# Nixie6_IN-12A_1_0.net
KiCad netlist of a schematic drawn in EAGLE
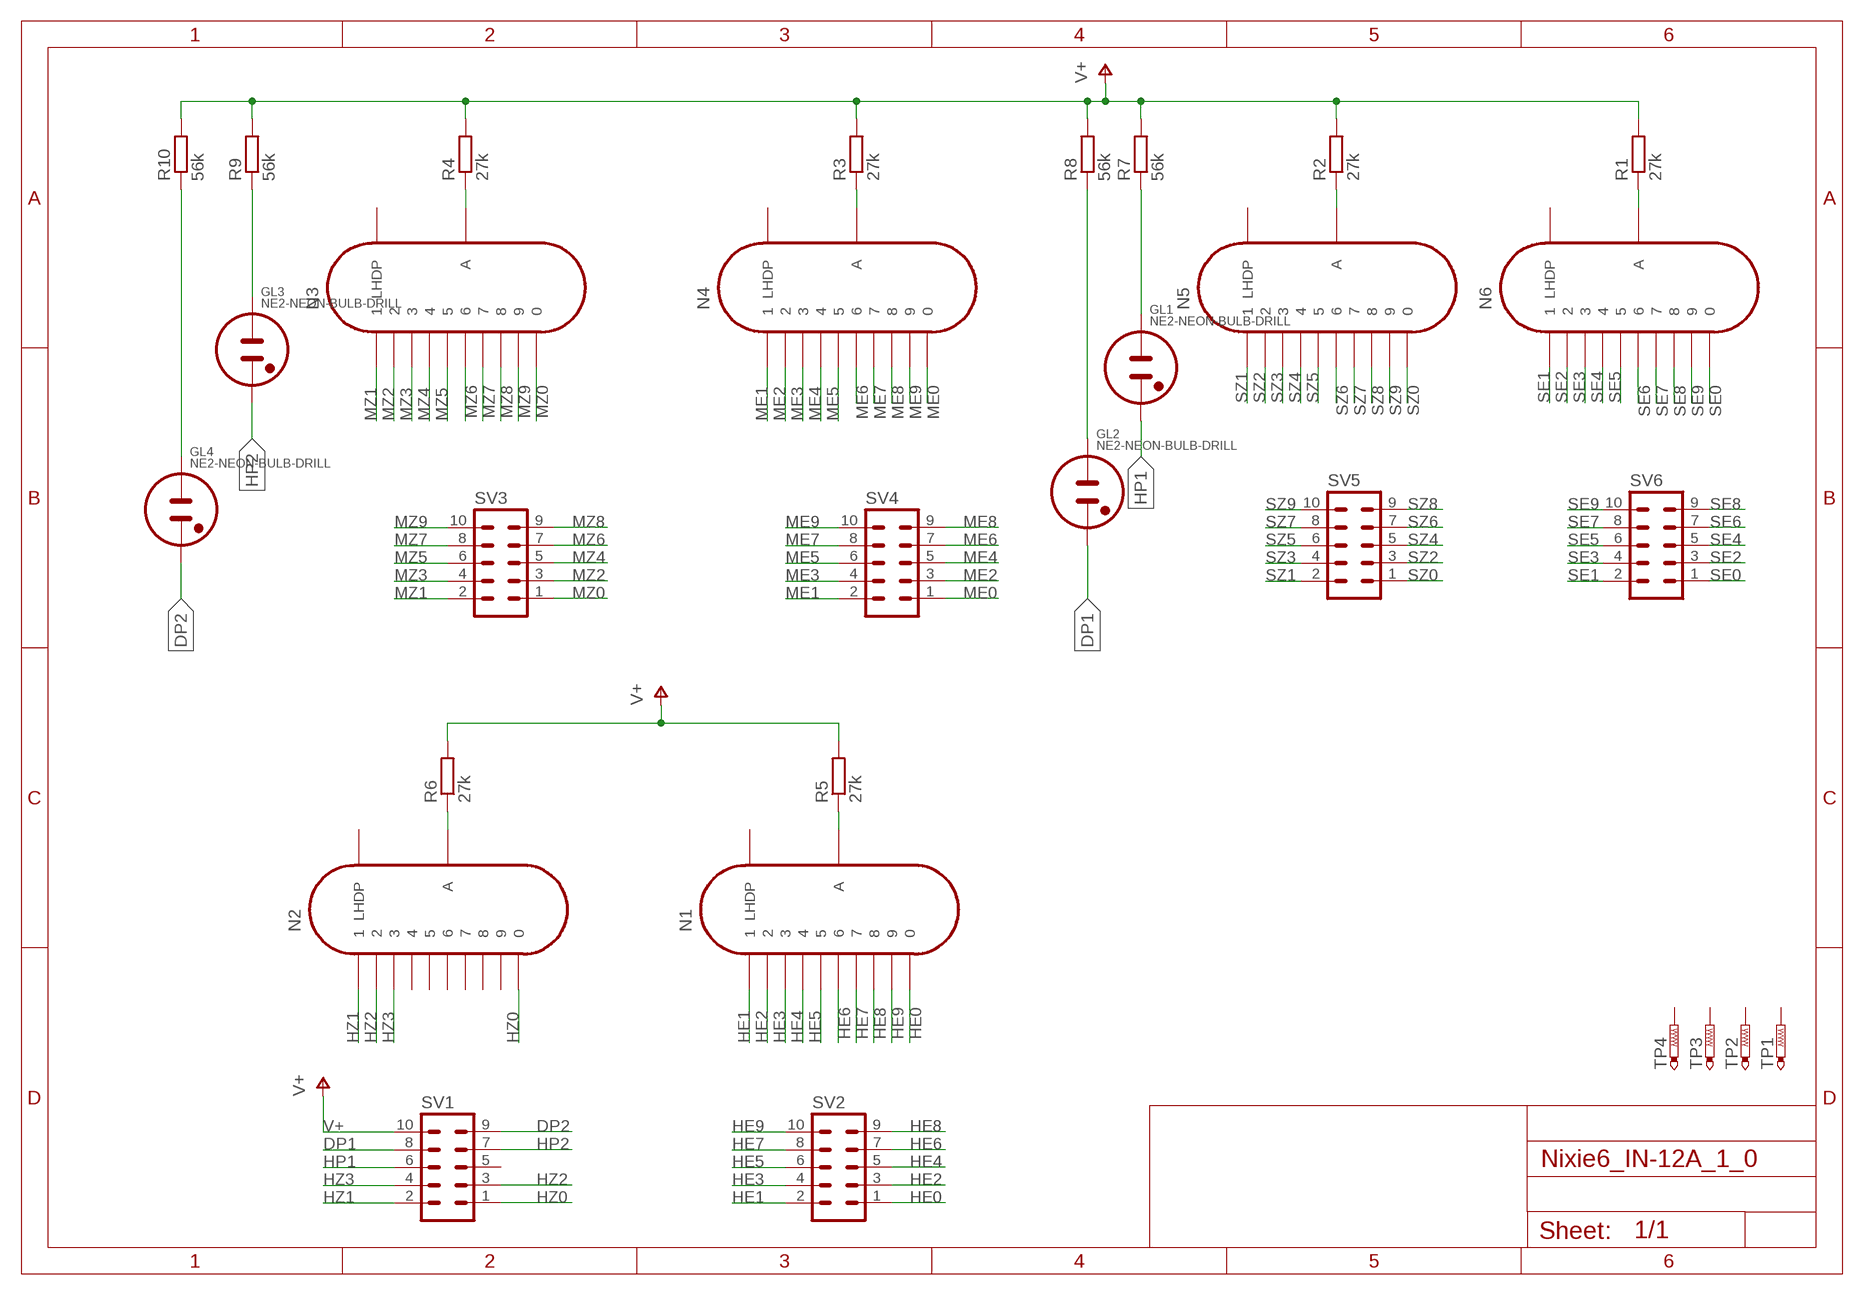
[diagram p0: schematic, sheet 1]

(export (version "E")
  (design (tool "Eeschema 10.0.6"))
  (components
    (comp (ref "GL1")
      (value "NE2-NEON-BULB-DRILL")
      (footprint "eagle-import:NE2-NEON-BULB-DRILL")
      (libsource (lib "eagle-import") (part "NE2-NEON-BULB-DRILL"))
    )
    (comp (ref "GL2")
      (value "NE2-NEON-BULB-DRILL")
      (footprint "eagle-import:NE2-NEON-BULB-DRILL")
      (libsource (lib "eagle-import") (part "NE2-NEON-BULB-DRILL"))
    )
    (comp (ref "GL3")
      (value "NE2-NEON-BULB-DRILL")
      (footprint "eagle-import:NE2-NEON-BULB-DRILL")
      (libsource (lib "eagle-import") (part "NE2-NEON-BULB-DRILL"))
    )
    (comp (ref "GL4")
      (value "NE2-NEON-BULB-DRILL")
      (footprint "eagle-import:NE2-NEON-BULB-DRILL")
      (libsource (lib "eagle-import") (part "NE2-NEON-BULB-DRILL"))
    )
    (comp (ref "N1")
      (value "IN-12B")
      (footprint "eagle-import:IN-12")
      (libsource (lib "eagle-import") (part "IN-12B"))
    )
    (comp (ref "N2")
      (value "IN-12B")
      (footprint "eagle-import:IN-12")
      (libsource (lib "eagle-import") (part "IN-12B"))
    )
    (comp (ref "N3")
      (value "IN-12B")
      (footprint "eagle-import:IN-12")
      (libsource (lib "eagle-import") (part "IN-12B"))
    )
    (comp (ref "N4")
      (value "IN-12B")
      (footprint "eagle-import:IN-12")
      (libsource (lib "eagle-import") (part "IN-12B"))
    )
    (comp (ref "N5")
      (value "IN-12B")
      (footprint "eagle-import:IN-12")
      (libsource (lib "eagle-import") (part "IN-12B"))
    )
    (comp (ref "N6")
      (value "IN-12B")
      (footprint "eagle-import:IN-12")
      (libsource (lib "eagle-import") (part "IN-12B"))
    )
    (comp (ref "R1")
      (value "27k")
      (footprint "eagle-import:0207_10")
      (libsource (lib "eagle-import") (part "R-EU_0207/10"))
    )
    (comp (ref "R2")
      (value "27k")
      (footprint "eagle-import:0207_10")
      (libsource (lib "eagle-import") (part "R-EU_0207/10"))
    )
    (comp (ref "R3")
      (value "27k")
      (footprint "eagle-import:0207_10")
      (libsource (lib "eagle-import") (part "R-EU_0207/10"))
    )
    (comp (ref "R4")
      (value "27k")
      (footprint "eagle-import:0207_10")
      (libsource (lib "eagle-import") (part "R-EU_0207/10"))
    )
    (comp (ref "R5")
      (value "27k")
      (footprint "eagle-import:0207_10")
      (libsource (lib "eagle-import") (part "R-EU_0207/10"))
    )
    (comp (ref "R6")
      (value "27k")
      (footprint "eagle-import:0207_10")
      (libsource (lib "eagle-import") (part "R-EU_0207/10"))
    )
    (comp (ref "R7")
      (value "56k")
      (footprint "eagle-import:0207_10")
      (libsource (lib "eagle-import") (part "R-EU_0207/10"))
    )
    (comp (ref "R8")
      (value "56k")
      (footprint "eagle-import:0207_10")
      (libsource (lib "eagle-import") (part "R-EU_0207/10"))
    )
    (comp (ref "R9")
      (value "56k")
      (footprint "eagle-import:0207_10")
      (libsource (lib "eagle-import") (part "R-EU_0207/10"))
    )
    (comp (ref "R10")
      (value "56k")
      (footprint "eagle-import:0207_10")
      (libsource (lib "eagle-import") (part "R-EU_0207/10"))
    )
    (comp (ref "SV1")
      (value "ML10")
      (footprint "eagle-import:ML10")
      (libsource (lib "eagle-import") (part "ML10"))
    )
    (comp (ref "SV2")
      (value "ML10")
      (footprint "eagle-import:ML10")
      (libsource (lib "eagle-import") (part "ML10"))
    )
    (comp (ref "SV3")
      (value "ML10")
      (footprint "eagle-import:ML10")
      (libsource (lib "eagle-import") (part "ML10"))
    )
    (comp (ref "SV4")
      (value "ML10")
      (footprint "eagle-import:ML10")
      (libsource (lib "eagle-import") (part "ML10"))
    )
    (comp (ref "SV5")
      (value "ML10")
      (footprint "eagle-import:ML10")
      (libsource (lib "eagle-import") (part "ML10"))
    )
    (comp (ref "SV6")
      (value "ML10")
      (footprint "eagle-import:ML10")
      (libsource (lib "eagle-import") (part "ML10"))
    )
    (comp (ref "TP1")
      (value "PTR1B1,27")
      (footprint "eagle-import:B1,27")
      (libsource (lib "eagle-import") (part "PTR1B1,27"))
    )
    (comp (ref "TP2")
      (value "PTR1B1,27")
      (footprint "eagle-import:B1,27")
      (libsource (lib "eagle-import") (part "PTR1B1,27"))
    )
    (comp (ref "TP3")
      (value "PTR1B1,27")
      (footprint "eagle-import:B1,27")
      (libsource (lib "eagle-import") (part "PTR1B1,27"))
    )
    (comp (ref "TP4")
      (value "PTR1B1,27")
      (footprint "eagle-import:B1,27")
      (libsource (lib "eagle-import") (part "PTR1B1,27"))
    )
  )
  (nets
    (net (code "1") (name "/HE0") (class "Default")
      (node (ref "N1") (pin "0") (pinfunction "0_0") (pintype "bidirectional"))
      (node (ref "SV2") (pin "1") (pinfunction "1_1") (pintype "passive"))
    )
    (net (code "2") (name "/HE1") (class "Default")
      (node (ref "N1") (pin "1") (pinfunction "1_1") (pintype "bidirectional"))
      (node (ref "SV2") (pin "2") (pinfunction "2_2") (pintype "passive"))
    )
    (net (code "3") (name "/HE2") (class "Default")
      (node (ref "N1") (pin "2") (pinfunction "2_2") (pintype "bidirectional"))
      (node (ref "SV2") (pin "3") (pinfunction "3_3") (pintype "passive"))
    )
    (net (code "4") (name "/HE3") (class "Default")
      (node (ref "N1") (pin "3") (pinfunction "3_3") (pintype "bidirectional"))
      (node (ref "SV2") (pin "4") (pinfunction "4_4") (pintype "passive"))
    )
    (net (code "5") (name "/HE4") (class "Default")
      (node (ref "N1") (pin "4") (pinfunction "4_4") (pintype "bidirectional"))
      (node (ref "SV2") (pin "5") (pinfunction "5_5") (pintype "passive"))
    )
    (net (code "6") (name "/HE5") (class "Default")
      (node (ref "N1") (pin "5") (pinfunction "5_5") (pintype "bidirectional"))
      (node (ref "SV2") (pin "6") (pinfunction "6_6") (pintype "passive"))
    )
    (net (code "7") (name "/HE6") (class "Default")
      (node (ref "N1") (pin "6") (pinfunction "6_6") (pintype "bidirectional"))
      (node (ref "SV2") (pin "7") (pinfunction "7_7") (pintype "passive"))
    )
    (net (code "8") (name "/HE7") (class "Default")
      (node (ref "N1") (pin "7") (pinfunction "7_7") (pintype "bidirectional"))
      (node (ref "SV2") (pin "8") (pinfunction "8_8") (pintype "passive"))
    )
    (net (code "9") (name "/HE8") (class "Default")
      (node (ref "N1") (pin "8") (pinfunction "8_8") (pintype "bidirectional"))
      (node (ref "SV2") (pin "9") (pinfunction "9_9") (pintype "passive"))
    )
    (net (code "10") (name "/HE9") (class "Default")
      (node (ref "N1") (pin "9") (pinfunction "9_9") (pintype "bidirectional"))
      (node (ref "SV2") (pin "10") (pinfunction "10_10") (pintype "passive"))
    )
    (net (code "11") (name "/HZ0") (class "Default")
      (node (ref "N2") (pin "0") (pinfunction "0_0") (pintype "bidirectional"))
      (node (ref "SV1") (pin "1") (pinfunction "1_1") (pintype "passive"))
    )
    (net (code "12") (name "/HZ1") (class "Default")
      (node (ref "N2") (pin "1") (pinfunction "1_1") (pintype "bidirectional"))
      (node (ref "SV1") (pin "2") (pinfunction "2_2") (pintype "passive"))
    )
    (net (code "13") (name "/HZ2") (class "Default")
      (node (ref "N2") (pin "2") (pinfunction "2_2") (pintype "bidirectional"))
      (node (ref "SV1") (pin "3") (pinfunction "3_3") (pintype "passive"))
    )
    (net (code "14") (name "/HZ3") (class "Default")
      (node (ref "N2") (pin "3") (pinfunction "3_3") (pintype "bidirectional"))
      (node (ref "SV1") (pin "4") (pinfunction "4_4") (pintype "passive"))
    )
    (net (code "15") (name "/ME0") (class "Default")
      (node (ref "N4") (pin "0") (pinfunction "0_0") (pintype "bidirectional"))
      (node (ref "SV4") (pin "1") (pinfunction "1_1") (pintype "passive"))
    )
    (net (code "16") (name "/ME1") (class "Default")
      (node (ref "N4") (pin "1") (pinfunction "1_1") (pintype "bidirectional"))
      (node (ref "SV4") (pin "2") (pinfunction "2_2") (pintype "passive"))
    )
    (net (code "17") (name "/ME2") (class "Default")
      (node (ref "N4") (pin "2") (pinfunction "2_2") (pintype "bidirectional"))
      (node (ref "SV4") (pin "3") (pinfunction "3_3") (pintype "passive"))
    )
    (net (code "18") (name "/ME3") (class "Default")
      (node (ref "N4") (pin "3") (pinfunction "3_3") (pintype "bidirectional"))
      (node (ref "SV4") (pin "4") (pinfunction "4_4") (pintype "passive"))
    )
    (net (code "19") (name "/ME4") (class "Default")
      (node (ref "N4") (pin "4") (pinfunction "4_4") (pintype "bidirectional"))
      (node (ref "SV4") (pin "5") (pinfunction "5_5") (pintype "passive"))
    )
    (net (code "20") (name "/ME5") (class "Default")
      (node (ref "N4") (pin "5") (pinfunction "5_5") (pintype "bidirectional"))
      (node (ref "SV4") (pin "6") (pinfunction "6_6") (pintype "passive"))
    )
    (net (code "21") (name "/ME6") (class "Default")
      (node (ref "N4") (pin "6") (pinfunction "6_6") (pintype "bidirectional"))
      (node (ref "SV4") (pin "7") (pinfunction "7_7") (pintype "passive"))
    )
    (net (code "22") (name "/ME7") (class "Default")
      (node (ref "N4") (pin "7") (pinfunction "7_7") (pintype "bidirectional"))
      (node (ref "SV4") (pin "8") (pinfunction "8_8") (pintype "passive"))
    )
    (net (code "23") (name "/ME8") (class "Default")
      (node (ref "N4") (pin "8") (pinfunction "8_8") (pintype "bidirectional"))
      (node (ref "SV4") (pin "9") (pinfunction "9_9") (pintype "passive"))
    )
    (net (code "24") (name "/ME9") (class "Default")
      (node (ref "N4") (pin "9") (pinfunction "9_9") (pintype "bidirectional"))
      (node (ref "SV4") (pin "10") (pinfunction "10_10") (pintype "passive"))
    )
    (net (code "25") (name "/MZ0") (class "Default")
      (node (ref "N3") (pin "0") (pinfunction "0_0") (pintype "bidirectional"))
      (node (ref "SV3") (pin "1") (pinfunction "1_1") (pintype "passive"))
    )
    (net (code "26") (name "/MZ1") (class "Default")
      (node (ref "N3") (pin "1") (pinfunction "1_1") (pintype "bidirectional"))
      (node (ref "SV3") (pin "2") (pinfunction "2_2") (pintype "passive"))
    )
    (net (code "27") (name "/MZ2") (class "Default")
      (node (ref "N3") (pin "2") (pinfunction "2_2") (pintype "bidirectional"))
      (node (ref "SV3") (pin "3") (pinfunction "3_3") (pintype "passive"))
    )
    (net (code "28") (name "/MZ3") (class "Default")
      (node (ref "N3") (pin "3") (pinfunction "3_3") (pintype "bidirectional"))
      (node (ref "SV3") (pin "4") (pinfunction "4_4") (pintype "passive"))
    )
    (net (code "29") (name "/MZ4") (class "Default")
      (node (ref "N3") (pin "4") (pinfunction "4_4") (pintype "bidirectional"))
      (node (ref "SV3") (pin "5") (pinfunction "5_5") (pintype "passive"))
    )
    (net (code "30") (name "/MZ5") (class "Default")
      (node (ref "N3") (pin "5") (pinfunction "5_5") (pintype "bidirectional"))
      (node (ref "SV3") (pin "6") (pinfunction "6_6") (pintype "passive"))
    )
    (net (code "31") (name "/MZ6") (class "Default")
      (node (ref "N3") (pin "6") (pinfunction "6_6") (pintype "bidirectional"))
      (node (ref "SV3") (pin "7") (pinfunction "7_7") (pintype "passive"))
    )
    (net (code "32") (name "/MZ7") (class "Default")
      (node (ref "N3") (pin "7") (pinfunction "7_7") (pintype "bidirectional"))
      (node (ref "SV3") (pin "8") (pinfunction "8_8") (pintype "passive"))
    )
    (net (code "33") (name "/MZ8") (class "Default")
      (node (ref "N3") (pin "8") (pinfunction "8_8") (pintype "bidirectional"))
      (node (ref "SV3") (pin "9") (pinfunction "9_9") (pintype "passive"))
    )
    (net (code "34") (name "/MZ9") (class "Default")
      (node (ref "N3") (pin "9") (pinfunction "9_9") (pintype "bidirectional"))
      (node (ref "SV3") (pin "10") (pinfunction "10_10") (pintype "passive"))
    )
    (net (code "35") (name "/SE0") (class "Default")
      (node (ref "N6") (pin "0") (pinfunction "0_0") (pintype "bidirectional"))
      (node (ref "SV6") (pin "1") (pinfunction "1_1") (pintype "passive"))
    )
    (net (code "36") (name "/SE1") (class "Default")
      (node (ref "N6") (pin "1") (pinfunction "1_1") (pintype "bidirectional"))
      (node (ref "SV6") (pin "2") (pinfunction "2_2") (pintype "passive"))
    )
    (net (code "37") (name "/SE2") (class "Default")
      (node (ref "N6") (pin "2") (pinfunction "2_2") (pintype "bidirectional"))
      (node (ref "SV6") (pin "3") (pinfunction "3_3") (pintype "passive"))
    )
    (net (code "38") (name "/SE3") (class "Default")
      (node (ref "N6") (pin "3") (pinfunction "3_3") (pintype "bidirectional"))
      (node (ref "SV6") (pin "4") (pinfunction "4_4") (pintype "passive"))
    )
    (net (code "39") (name "/SE4") (class "Default")
      (node (ref "N6") (pin "4") (pinfunction "4_4") (pintype "bidirectional"))
      (node (ref "SV6") (pin "5") (pinfunction "5_5") (pintype "passive"))
    )
    (net (code "40") (name "/SE5") (class "Default")
      (node (ref "N6") (pin "5") (pinfunction "5_5") (pintype "bidirectional"))
      (node (ref "SV6") (pin "6") (pinfunction "6_6") (pintype "passive"))
    )
    (net (code "41") (name "/SE6") (class "Default")
      (node (ref "N6") (pin "6") (pinfunction "6_6") (pintype "bidirectional"))
      (node (ref "SV6") (pin "7") (pinfunction "7_7") (pintype "passive"))
    )
    (net (code "42") (name "/SE7") (class "Default")
      (node (ref "N6") (pin "7") (pinfunction "7_7") (pintype "bidirectional"))
      (node (ref "SV6") (pin "8") (pinfunction "8_8") (pintype "passive"))
    )
    (net (code "43") (name "/SE8") (class "Default")
      (node (ref "N6") (pin "8") (pinfunction "8_8") (pintype "bidirectional"))
      (node (ref "SV6") (pin "9") (pinfunction "9_9") (pintype "passive"))
    )
    (net (code "44") (name "/SE9") (class "Default")
      (node (ref "N6") (pin "9") (pinfunction "9_9") (pintype "bidirectional"))
      (node (ref "SV6") (pin "10") (pinfunction "10_10") (pintype "passive"))
    )
    (net (code "45") (name "/SZ0") (class "Default")
      (node (ref "N5") (pin "0") (pinfunction "0_0") (pintype "bidirectional"))
      (node (ref "SV5") (pin "1") (pinfunction "1_1") (pintype "passive"))
    )
    (net (code "46") (name "/SZ1") (class "Default")
      (node (ref "N5") (pin "1") (pinfunction "1_1") (pintype "bidirectional"))
      (node (ref "SV5") (pin "2") (pinfunction "2_2") (pintype "passive"))
    )
    (net (code "47") (name "/SZ2") (class "Default")
      (node (ref "N5") (pin "2") (pinfunction "2_2") (pintype "bidirectional"))
      (node (ref "SV5") (pin "3") (pinfunction "3_3") (pintype "passive"))
    )
    (net (code "48") (name "/SZ3") (class "Default")
      (node (ref "N5") (pin "3") (pinfunction "3_3") (pintype "bidirectional"))
      (node (ref "SV5") (pin "4") (pinfunction "4_4") (pintype "passive"))
    )
    (net (code "49") (name "/SZ4") (class "Default")
      (node (ref "N5") (pin "4") (pinfunction "4_4") (pintype "bidirectional"))
      (node (ref "SV5") (pin "5") (pinfunction "5_5") (pintype "passive"))
    )
    (net (code "50") (name "/SZ5") (class "Default")
      (node (ref "N5") (pin "5") (pinfunction "5_5") (pintype "bidirectional"))
      (node (ref "SV5") (pin "6") (pinfunction "6_6") (pintype "passive"))
    )
    (net (code "51") (name "/SZ6") (class "Default")
      (node (ref "N5") (pin "6") (pinfunction "6_6") (pintype "bidirectional"))
      (node (ref "SV5") (pin "7") (pinfunction "7_7") (pintype "passive"))
    )
    (net (code "52") (name "/SZ7") (class "Default")
      (node (ref "N5") (pin "7") (pinfunction "7_7") (pintype "bidirectional"))
      (node (ref "SV5") (pin "8") (pinfunction "8_8") (pintype "passive"))
    )
    (net (code "53") (name "/SZ8") (class "Default")
      (node (ref "N5") (pin "8") (pinfunction "8_8") (pintype "bidirectional"))
      (node (ref "SV5") (pin "9") (pinfunction "9_9") (pintype "passive"))
    )
    (net (code "54") (name "/SZ9") (class "Default")
      (node (ref "N5") (pin "9") (pinfunction "9_9") (pintype "bidirectional"))
      (node (ref "SV5") (pin "10") (pinfunction "10_10") (pintype "passive"))
    )
    (net (code "55") (name "DP1") (class "Default")
      (node (ref "GL2") (pin "2") (pinfunction "A1_2") (pintype "passive"))
      (node (ref "SV1") (pin "8") (pinfunction "8_8") (pintype "passive"))
    )
    (net (code "56") (name "DP2") (class "Default")
      (node (ref "GL4") (pin "2") (pinfunction "A1_2") (pintype "passive"))
      (node (ref "SV1") (pin "9") (pinfunction "9_9") (pintype "passive"))
    )
    (net (code "57") (name "HP1") (class "Default")
      (node (ref "GL1") (pin "2") (pinfunction "A1_2") (pintype "passive"))
      (node (ref "SV1") (pin "6") (pinfunction "6_6") (pintype "passive"))
    )
    (net (code "58") (name "HP2") (class "Default")
      (node (ref "GL3") (pin "2") (pinfunction "A1_2") (pintype "passive"))
      (node (ref "SV1") (pin "7") (pinfunction "7_7") (pintype "passive"))
    )
    (net (code "59") (name "Net-(GL1-A)") (class "Default")
      (node (ref "GL1") (pin "1") (pinfunction "A_1") (pintype "passive"))
      (node (ref "R7") (pin "1") (pinfunction "1_1") (pintype "passive"))
    )
    (net (code "60") (name "Net-(GL2-A)") (class "Default")
      (node (ref "GL2") (pin "1") (pinfunction "A_1") (pintype "passive"))
      (node (ref "R8") (pin "1") (pinfunction "1_1") (pintype "passive"))
    )
    (net (code "61") (name "Net-(GL3-A)") (class "Default")
      (node (ref "GL3") (pin "1") (pinfunction "A_1") (pintype "passive"))
      (node (ref "R9") (pin "1") (pinfunction "1_1") (pintype "passive"))
    )
    (net (code "62") (name "Net-(GL4-A)") (class "Default")
      (node (ref "GL4") (pin "1") (pinfunction "A_1") (pintype "passive"))
      (node (ref "R10") (pin "1") (pinfunction "1_1") (pintype "passive"))
    )
    (net (code "63") (name "Net-(N1-PadA)") (class "Default")
      (node (ref "N1") (pin "A") (pinfunction "A_A") (pintype "bidirectional"))
      (node (ref "R5") (pin "1") (pinfunction "1_1") (pintype "passive"))
    )
    (net (code "64") (name "Net-(N2-PadA)") (class "Default")
      (node (ref "N2") (pin "A") (pinfunction "A_A") (pintype "bidirectional"))
      (node (ref "R6") (pin "1") (pinfunction "1_1") (pintype "passive"))
    )
    (net (code "65") (name "Net-(N3-PadA)") (class "Default")
      (node (ref "N3") (pin "A") (pinfunction "A_A") (pintype "bidirectional"))
      (node (ref "R4") (pin "1") (pinfunction "1_1") (pintype "passive"))
    )
    (net (code "66") (name "Net-(N4-PadA)") (class "Default")
      (node (ref "N4") (pin "A") (pinfunction "A_A") (pintype "bidirectional"))
      (node (ref "R3") (pin "1") (pinfunction "1_1") (pintype "passive"))
    )
    (net (code "67") (name "Net-(N5-PadA)") (class "Default")
      (node (ref "N5") (pin "A") (pinfunction "A_A") (pintype "bidirectional"))
      (node (ref "R2") (pin "1") (pinfunction "1_1") (pintype "passive"))
    )
    (net (code "68") (name "Net-(N6-PadA)") (class "Default")
      (node (ref "N6") (pin "A") (pinfunction "A_A") (pintype "bidirectional"))
      (node (ref "R1") (pin "1") (pinfunction "1_1") (pintype "passive"))
    )
    (net (code "69") (name "V+") (class "Default")
      (node (ref "R1") (pin "2") (pinfunction "2_2") (pintype "passive"))
      (node (ref "R10") (pin "2") (pinfunction "2_2") (pintype "passive"))
      (node (ref "R2") (pin "2") (pinfunction "2_2") (pintype "passive"))
      (node (ref "R3") (pin "2") (pinfunction "2_2") (pintype "passive"))
      (node (ref "R4") (pin "2") (pinfunction "2_2") (pintype "passive"))
      (node (ref "R5") (pin "2") (pinfunction "2_2") (pintype "passive"))
      (node (ref "R6") (pin "2") (pinfunction "2_2") (pintype "passive"))
      (node (ref "R7") (pin "2") (pinfunction "2_2") (pintype "passive"))
      (node (ref "R8") (pin "2") (pinfunction "2_2") (pintype "passive"))
      (node (ref "R9") (pin "2") (pinfunction "2_2") (pintype "passive"))
      (node (ref "SV1") (pin "10") (pinfunction "10_10") (pintype "passive"))
    )
    (net (code "70") (name "unconnected-(N1-PadLHDP)") (class "Default")
      (node (ref "N1") (pin "LHDP") (pinfunction "LHDP_LHDP") (pintype "bidirectional"))
    )
    (net (code "71") (name "unconnected-(N2-Pad4)") (class "Default")
      (node (ref "N2") (pin "4") (pinfunction "4_4") (pintype "bidirectional"))
    )
    (net (code "72") (name "unconnected-(N2-Pad5)") (class "Default")
      (node (ref "N2") (pin "5") (pinfunction "5_5") (pintype "bidirectional"))
    )
    (net (code "73") (name "unconnected-(N2-Pad6)") (class "Default")
      (node (ref "N2") (pin "6") (pinfunction "6_6") (pintype "bidirectional"))
    )
    (net (code "74") (name "unconnected-(N2-Pad7)") (class "Default")
      (node (ref "N2") (pin "7") (pinfunction "7_7") (pintype "bidirectional"))
    )
    (net (code "75") (name "unconnected-(N2-Pad8)") (class "Default")
      (node (ref "N2") (pin "8") (pinfunction "8_8") (pintype "bidirectional"))
    )
    (net (code "76") (name "unconnected-(N2-Pad9)") (class "Default")
      (node (ref "N2") (pin "9") (pinfunction "9_9") (pintype "bidirectional"))
    )
    (net (code "77") (name "unconnected-(N2-PadLHDP)") (class "Default")
      (node (ref "N2") (pin "LHDP") (pinfunction "LHDP_LHDP") (pintype "bidirectional"))
    )
    (net (code "78") (name "unconnected-(N3-PadLHDP)") (class "Default")
      (node (ref "N3") (pin "LHDP") (pinfunction "LHDP_LHDP") (pintype "bidirectional"))
    )
    (net (code "79") (name "unconnected-(N4-PadLHDP)") (class "Default")
      (node (ref "N4") (pin "LHDP") (pinfunction "LHDP_LHDP") (pintype "bidirectional"))
    )
    (net (code "80") (name "unconnected-(N5-PadLHDP)") (class "Default")
      (node (ref "N5") (pin "LHDP") (pinfunction "LHDP_LHDP") (pintype "bidirectional"))
    )
    (net (code "81") (name "unconnected-(N6-PadLHDP)") (class "Default")
      (node (ref "N6") (pin "LHDP") (pinfunction "LHDP_LHDP") (pintype "bidirectional"))
    )
    (net (code "82") (name "unconnected-(SV1-Pad5)") (class "Default")
      (node (ref "SV1") (pin "5") (pinfunction "5_5") (pintype "passive"))
    )
    (net (code "83") (name "unconnected-(TP1-PadTP)") (class "Default")
      (node (ref "TP1") (pin "TP") (pinfunction "TP_TP") (pintype "input"))
    )
    (net (code "84") (name "unconnected-(TP2-PadTP)") (class "Default")
      (node (ref "TP2") (pin "TP") (pinfunction "TP_TP") (pintype "input"))
    )
    (net (code "85") (name "unconnected-(TP3-PadTP)") (class "Default")
      (node (ref "TP3") (pin "TP") (pinfunction "TP_TP") (pintype "input"))
    )
    (net (code "86") (name "unconnected-(TP4-PadTP)") (class "Default")
      (node (ref "TP4") (pin "TP") (pinfunction "TP_TP") (pintype "input"))
    )
  )
)
